# artik530_carrierboard.net
KiCad netlist of a schematic drawn in EAGLE
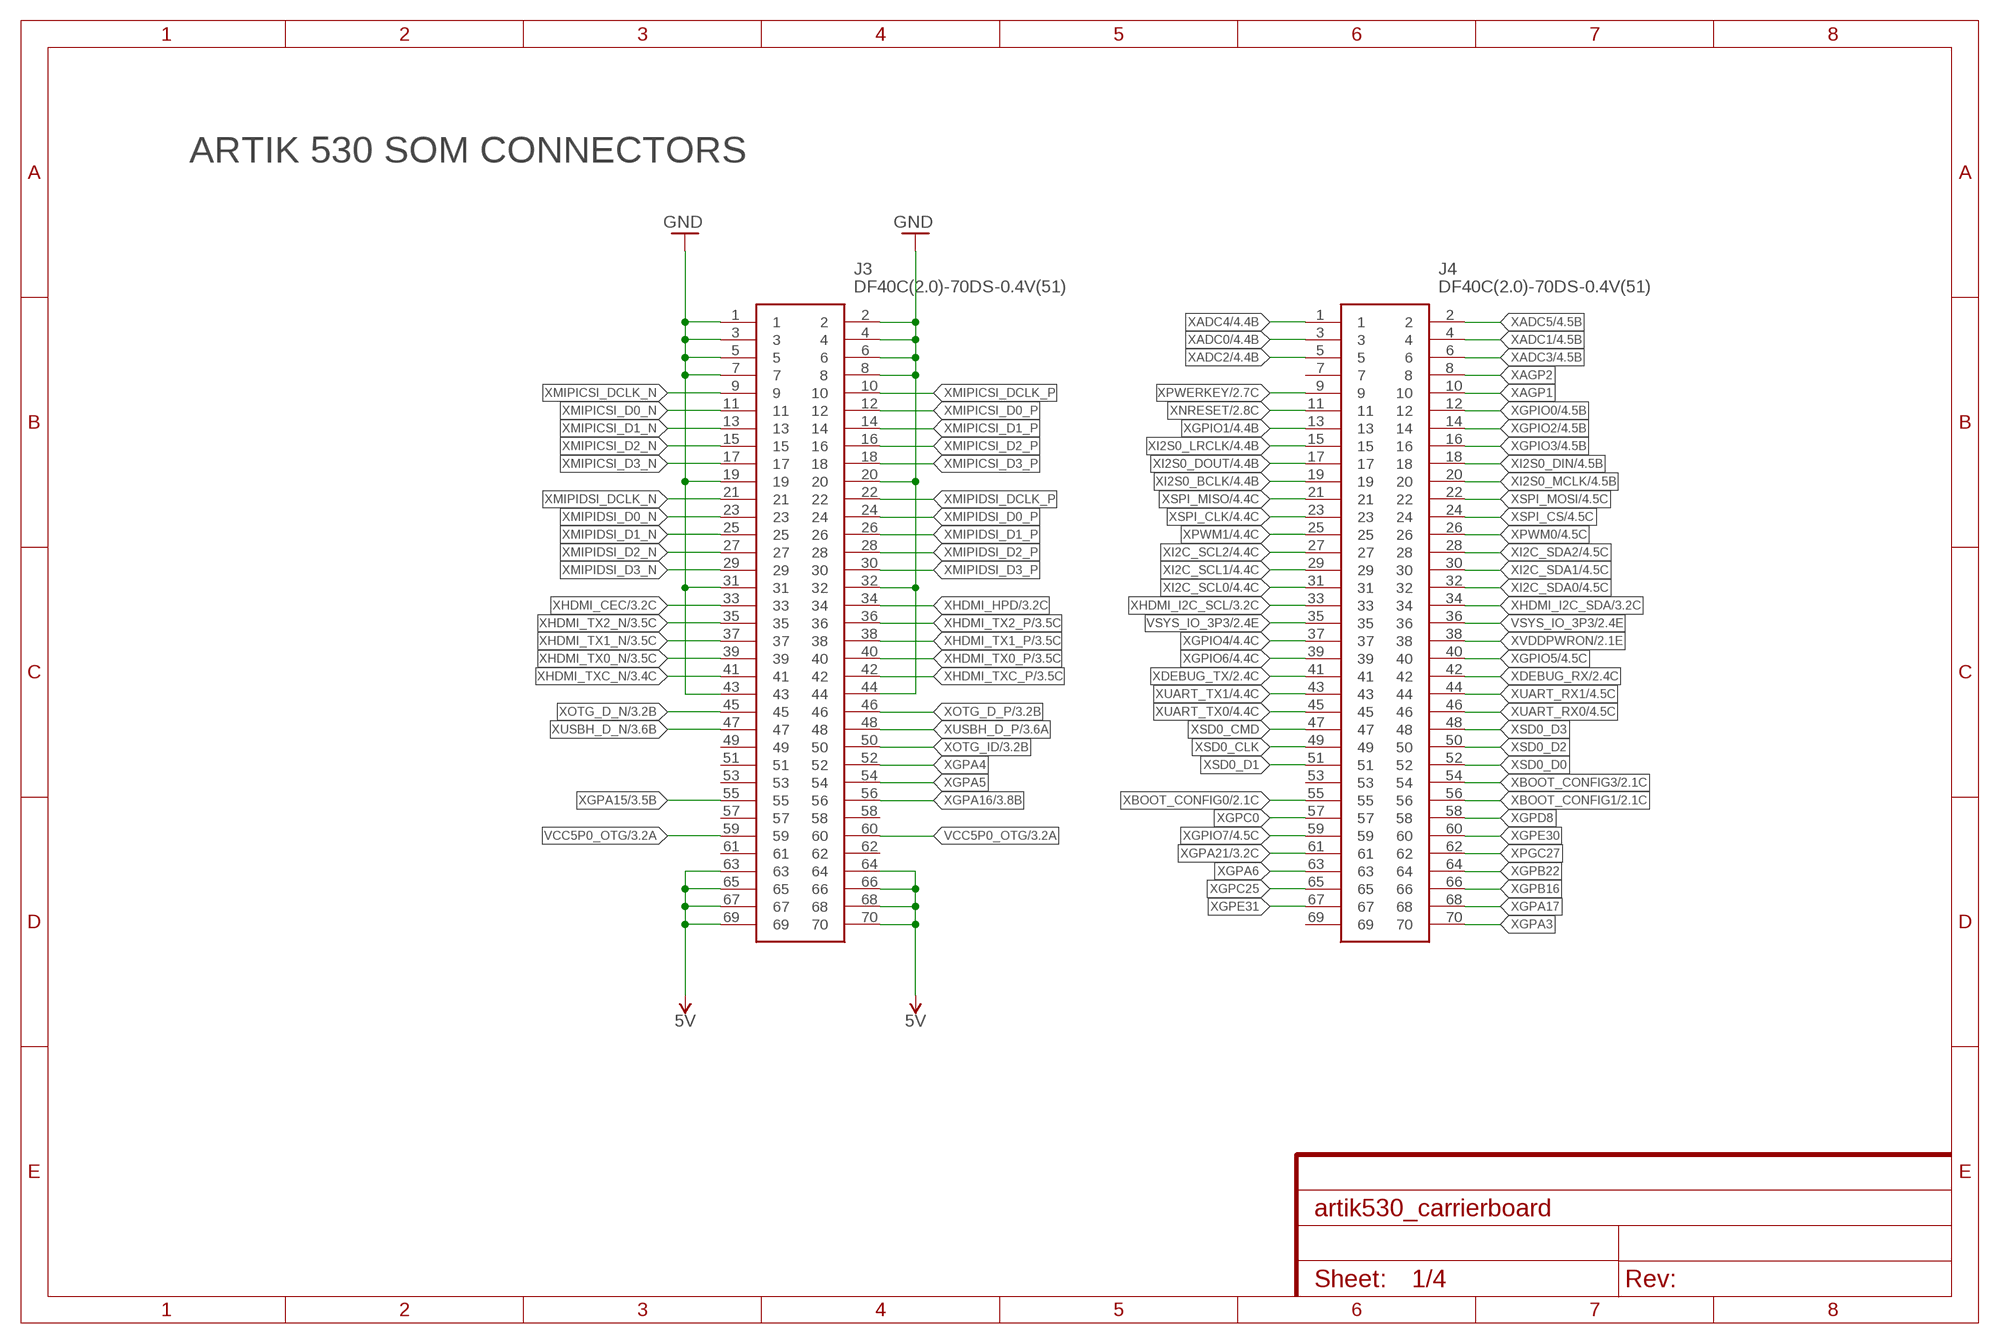
[diagram p0: schematic, sheet 1]
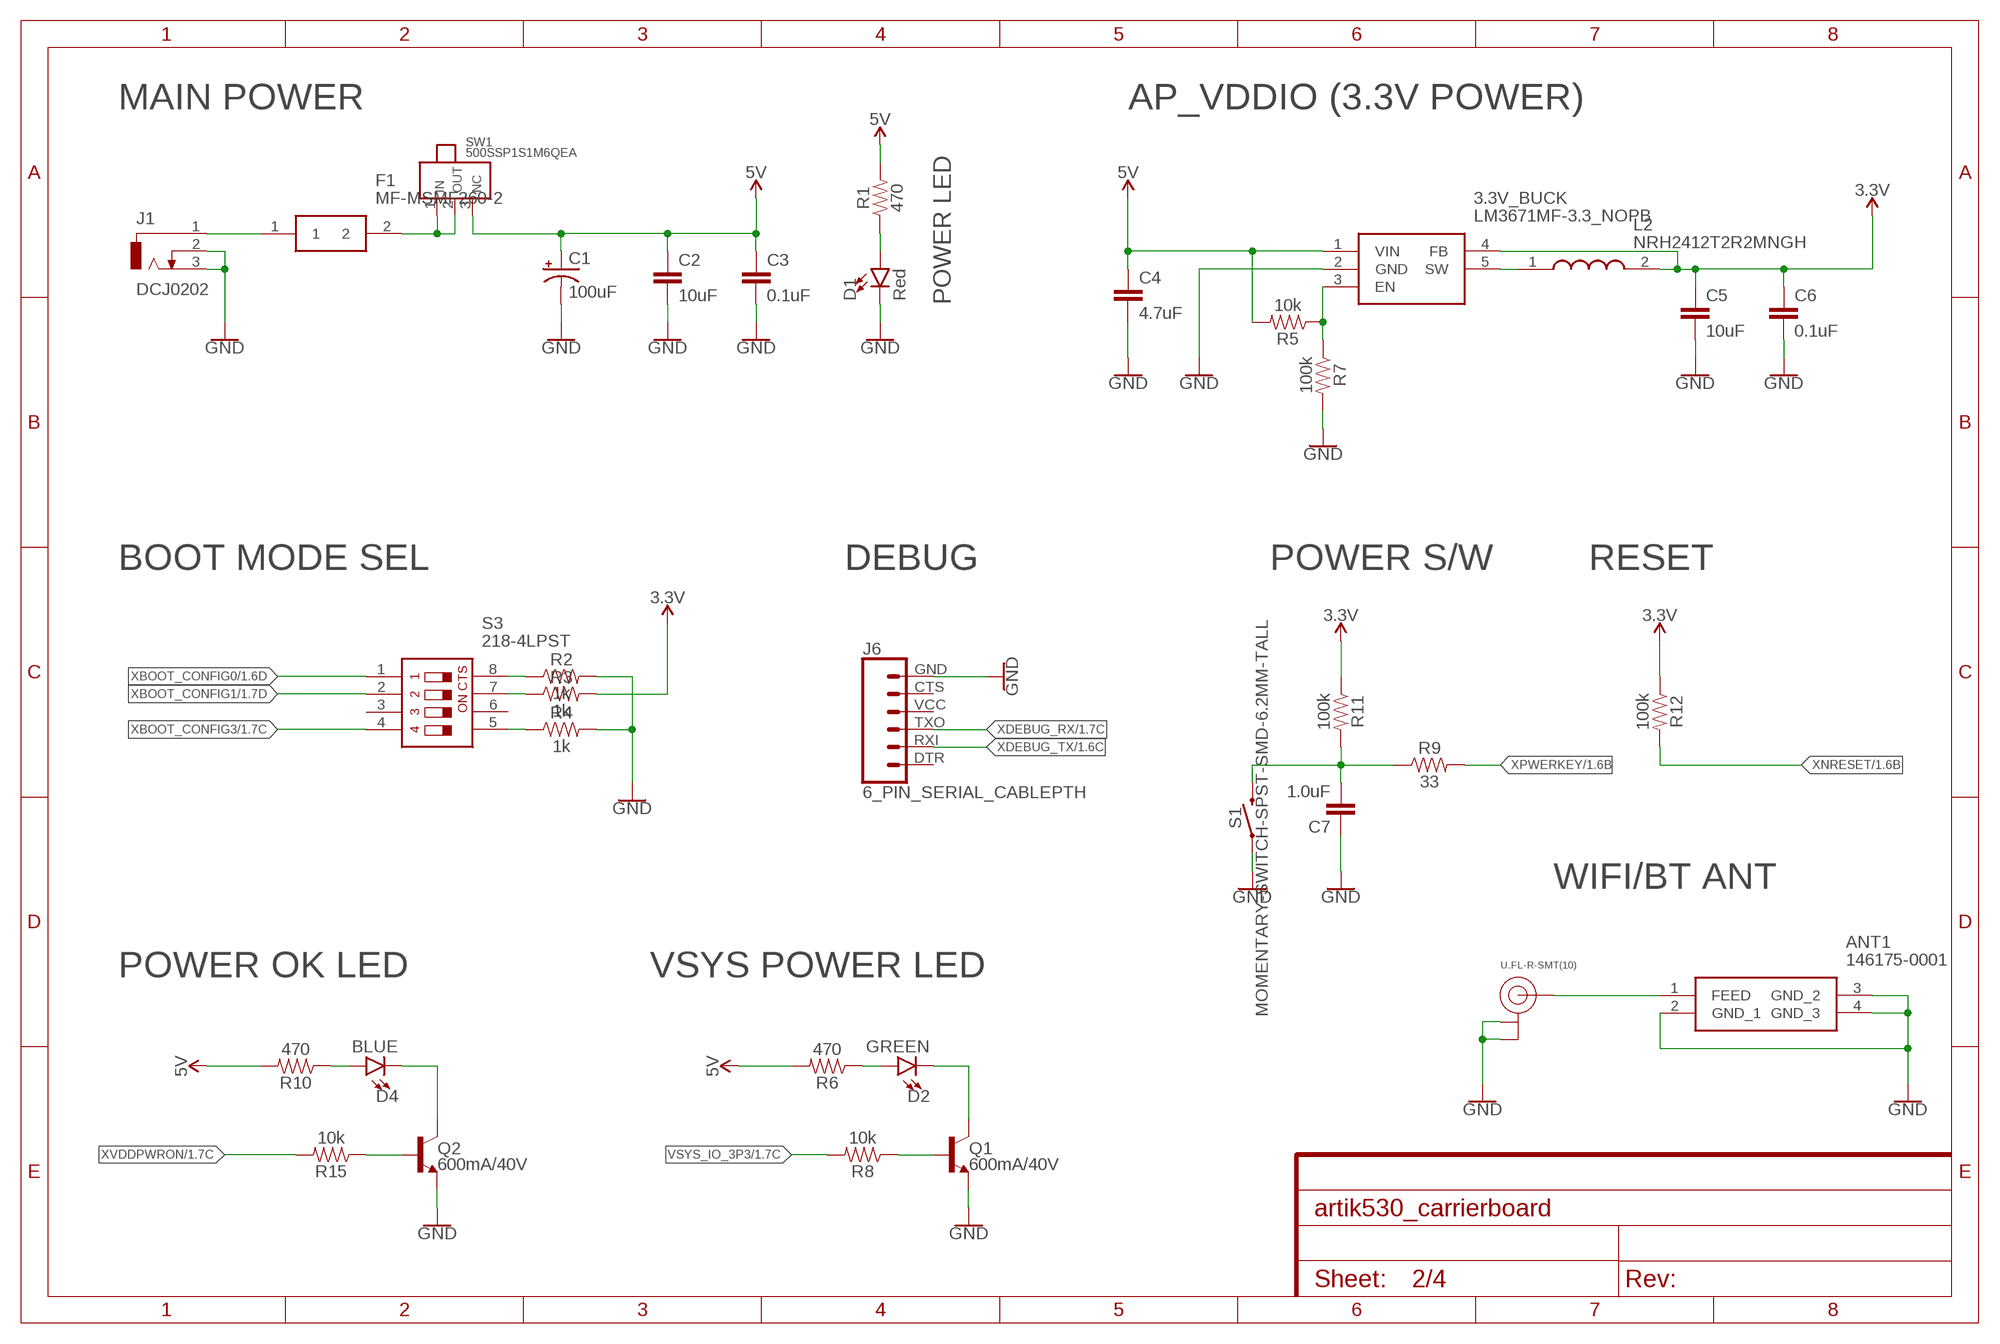
[diagram p1: schematic, sheet 2]
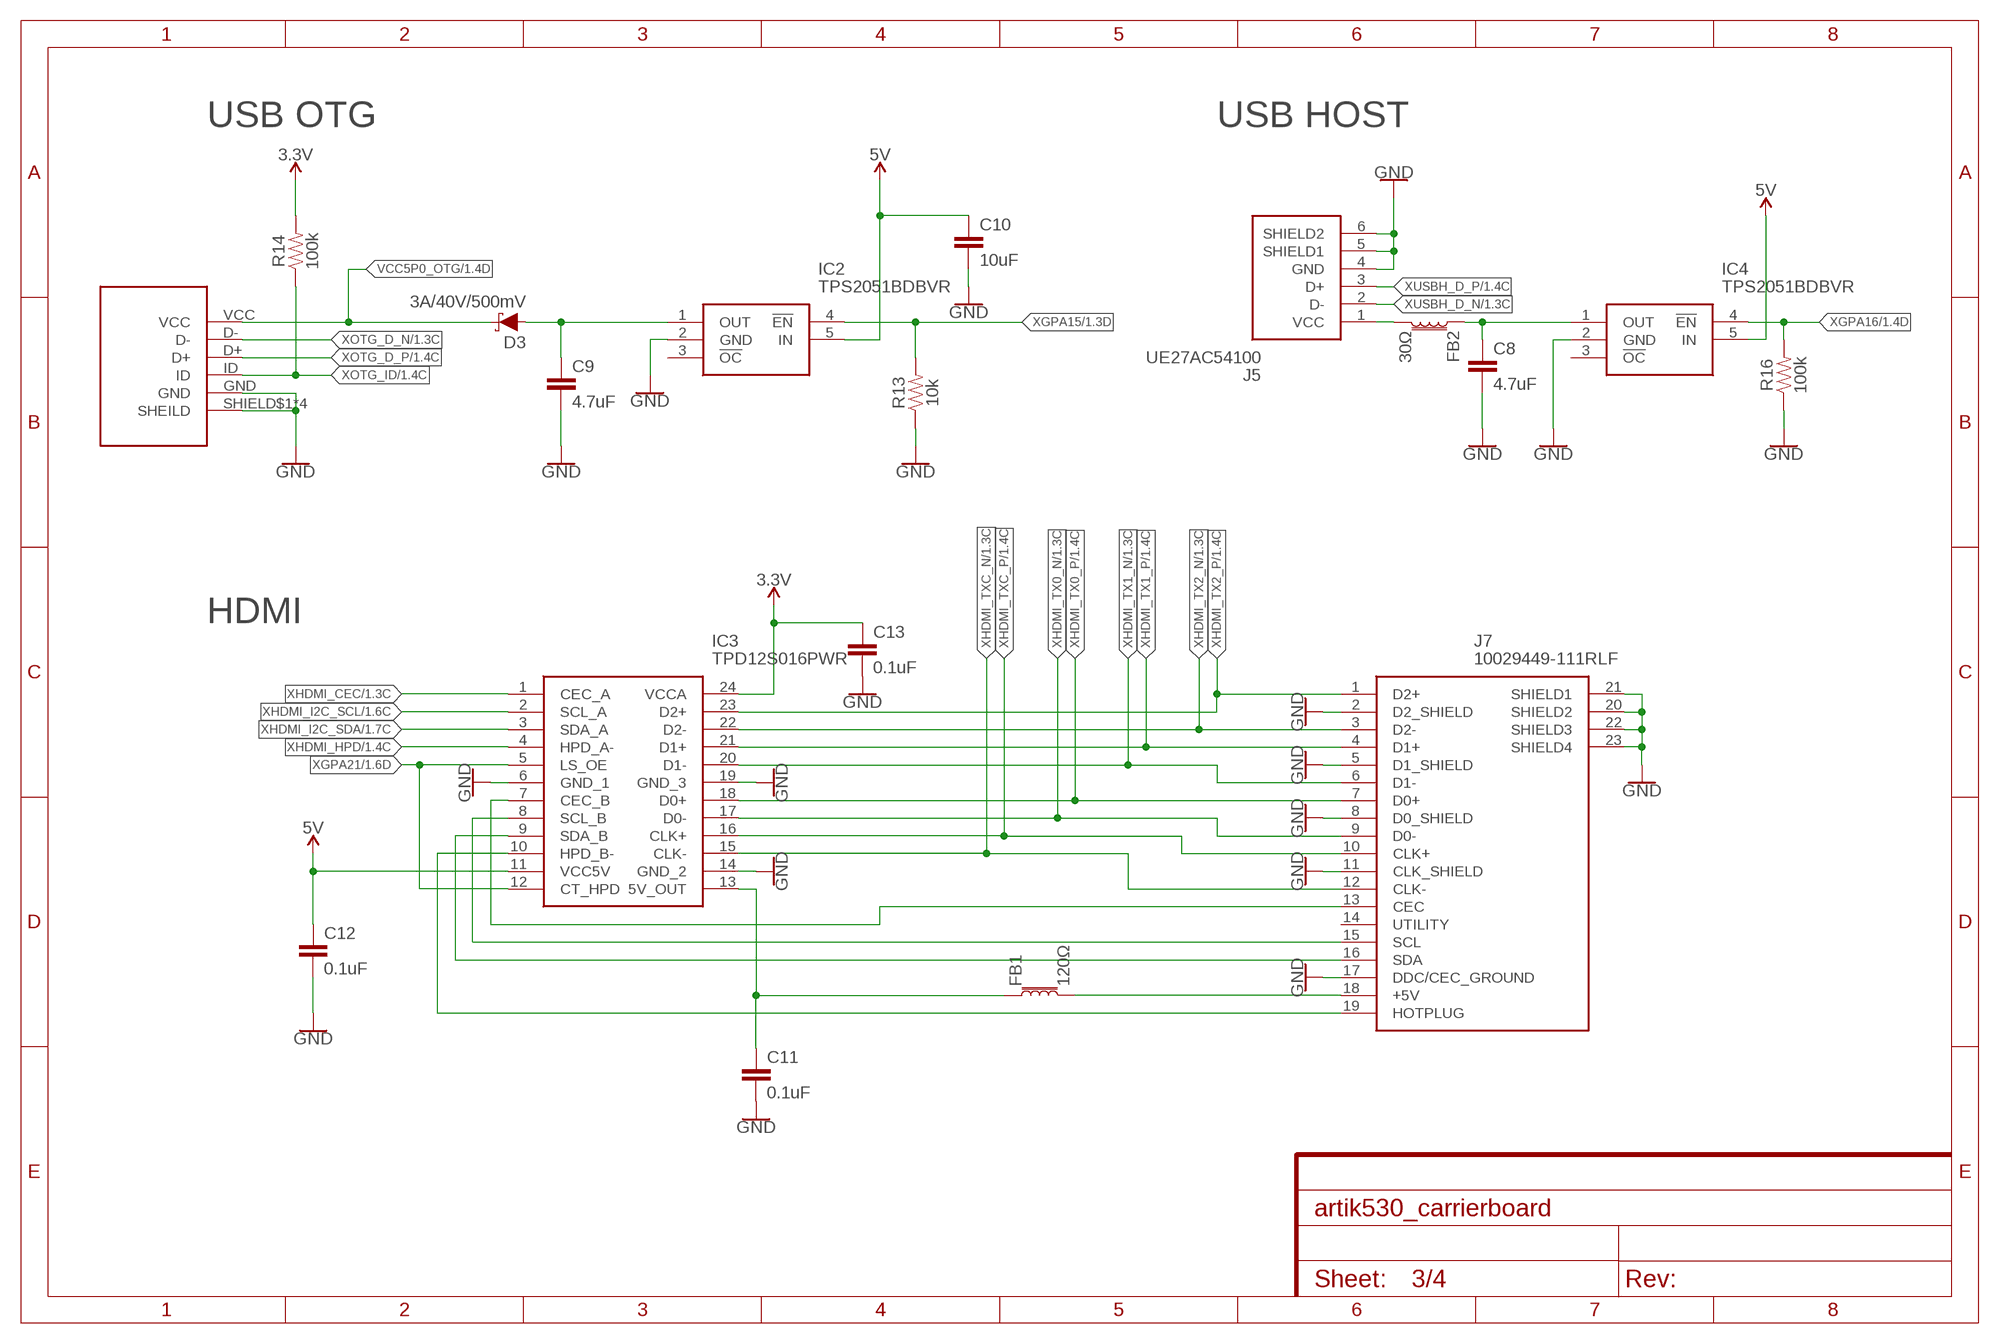
[diagram p2: schematic, sheet 3]
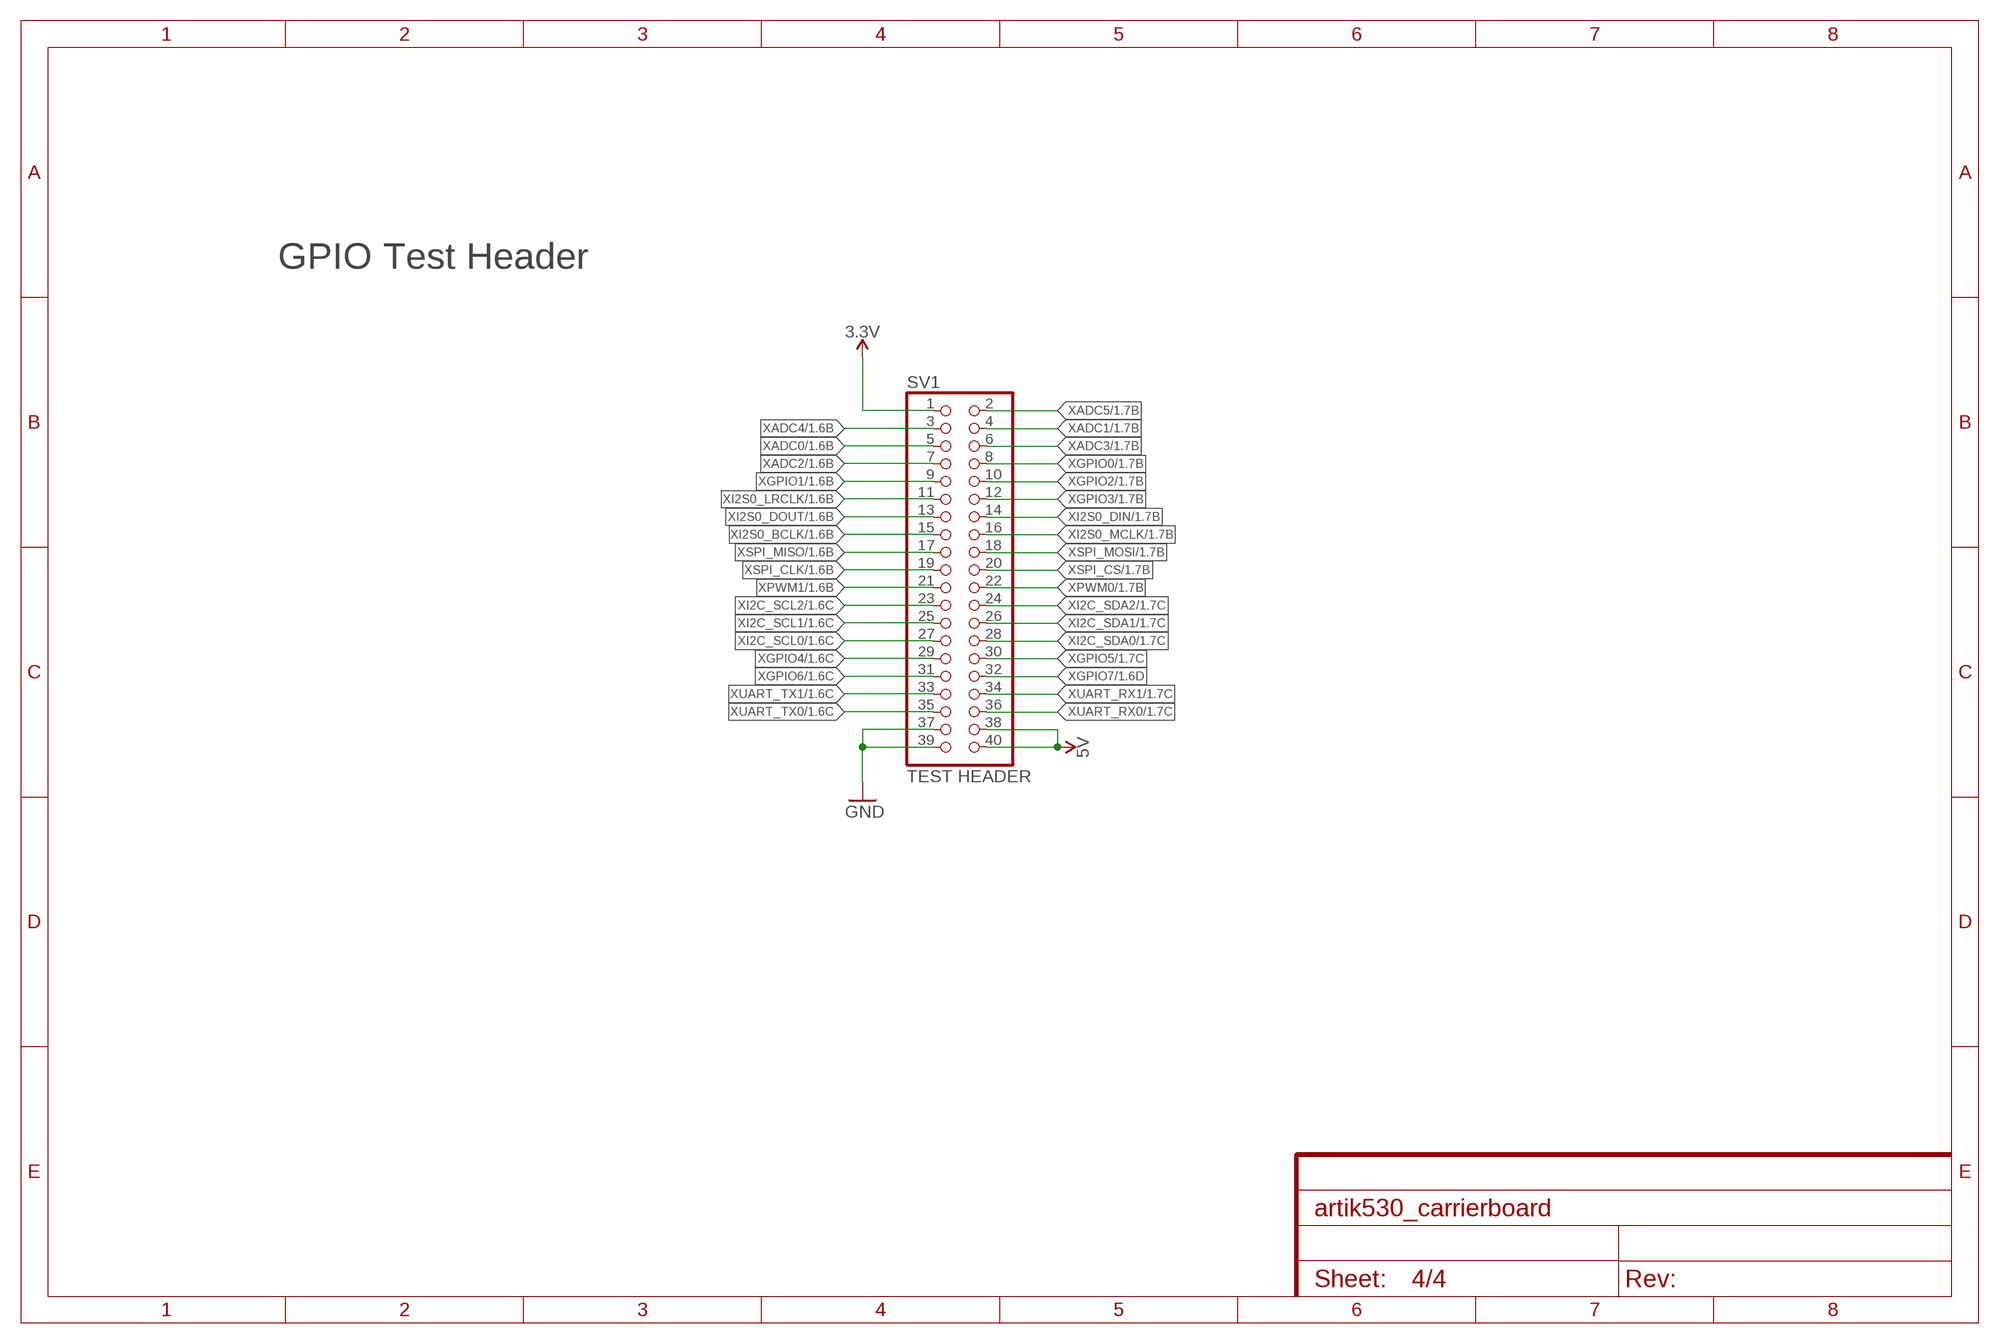
[diagram p3: schematic, sheet 4]

(export (version "E")
  (design (tool "Eeschema 10.0.6"))
  (components
    (comp (ref "C8")
      (value "4.7uF")
      (footprint "eagle-import:0603")
      (libsource (lib "eagle-import") (part "4.7UF-0603-6.3V-(10%)"))
    )
    (comp (ref "C9")
      (value "4.7uF")
      (footprint "eagle-import:0603")
      (libsource (lib "eagle-import") (part "4.7UF-0603-6.3V-(10%)"))
    )
    (comp (ref "C10")
      (value "10uF")
      (footprint "eagle-import:0603")
      (libsource (lib "eagle-import") (part "10UF-0603-6.3V-20%"))
    )
    (comp (ref "C11")
      (value "0.1uF")
      (footprint "eagle-import:0603")
      (libsource (lib "eagle-import") (part "0.1UF-0603-25V-(+80/-20%)"))
    )
    (comp (ref "C12")
      (value "0.1uF")
      (footprint "eagle-import:0603")
      (libsource (lib "eagle-import") (part "0.1UF-0603-25V-(+80/-20%)"))
    )
    (comp (ref "C13")
      (value "0.1uF")
      (footprint "eagle-import:0603")
      (libsource (lib "eagle-import") (part "0.1UF-0603-25V-(+80/-20%)"))
    )
    (comp (ref "D3")
      (value "3A/40V/500mV")
      (footprint "eagle-import:SMA-DIODE")
      (libsource (lib "eagle-import") (part "DIODE-SCHOTTKY-B340A"))
    )
    (comp (ref "FB1")
      (value "120Ω")
      (footprint "eagle-import:0603")
      (libsource (lib "eagle-import") (part "FERRITE_BEAD-0603"))
    )
    (comp (ref "FB2")
      (value "30Ω")
      (footprint "eagle-import:0603")
      (libsource (lib "eagle-import") (part "FERRITE_BEAD-0603"))
    )
    (comp (ref "IC2")
      (value "TPS2051BDBVR")
      (footprint "eagle-import:SOT95P280X145-5N")
      (libsource (lib "eagle-import") (part "TPS2051BDBVR"))
    )
    (comp (ref "IC3")
      (value "TPD12S016PWR")
      (footprint "eagle-import:SOP65P640X120-24N")
      (fields (field (name "RS_PART_NUMBER") "1627865"))
      (libsource (lib "eagle-import") (part "TPD12S016PWR"))
    )
    (comp (ref "IC4")
      (value "TPS2051BDBVR")
      (footprint "eagle-import:SOT95P280X145-5N")
      (libsource (lib "eagle-import") (part "TPS2051BDBVR"))
    )
    (comp (ref "J2")
      (value "10118193-0001LF")
      (footprint "eagle-import:10118193-0001LF")
      (libsource (lib "eagle-import") (part "10118193-0001LF"))
    )
    (comp (ref "J5")
      (value "UE27AC54100")
      (footprint "eagle-import:UE27AC54100")
      (libsource (lib "eagle-import") (part "UE27AC54100"))
    )
    (comp (ref "J7")
      (value "10029449-111RLF")
      (footprint "eagle-import:10029449-111RLF_1")
      (libsource (lib "eagle-import") (part "10029449-111RLF"))
    )
    (comp (ref "R13")
      (value "10k")
      (footprint "eagle-import:0603")
      (libsource (lib "eagle-import") (part "10KOHM-0603-1/10W-1%"))
    )
    (comp (ref "R14")
      (value "100k")
      (footprint "eagle-import:0603")
      (libsource (lib "eagle-import") (part "100KOHM-0603-1/10W-1%"))
    )
    (comp (ref "R16")
      (value "100k")
      (footprint "eagle-import:0603")
      (libsource (lib "eagle-import") (part "100KOHM-0603-1/10W-1%"))
    )
    (comp (ref "3.3V_BUCK")
      (value "LM3671MF-3.3_NOPB")
      (footprint "eagle-import:SOT95P284X122-5N")
      (fields
        (field (name "DIGIKEY_PART_NUMBER") "LM3671MF-3.3/NOPBTR-ND")
        (field (name "MANUFACTURER_PART_NUMBER") "LM3671MF-3.3/NOPB")
      )
      (libsource (lib "eagle-import") (part "LM3671MF-3.3_NOPB"))
    )
    (comp (ref "ANT1")
      (value "146175-0001")
      (footprint "eagle-import:146175-0001")
      (libsource (lib "eagle-import") (part "146175-0001"))
    )
    (comp (ref "C1")
      (value "100uF")
      (footprint "eagle-import:EIA7343")
      (libsource (lib "eagle-import") (part "100UF-POLAR-EIA7343-10V-10%(TANT)"))
    )
    (comp (ref "C2")
      (value "10uF")
      (footprint "eagle-import:0603")
      (libsource (lib "eagle-import") (part "10UF-0603-6.3V-20%"))
    )
    (comp (ref "C3")
      (value "0.1uF")
      (footprint "eagle-import:0603")
      (libsource (lib "eagle-import") (part "0.1UF-0603-25V-(+80/-20%)"))
    )
    (comp (ref "C4")
      (value "4.7uF")
      (footprint "eagle-import:0603")
      (libsource (lib "eagle-import") (part "4.7UF-0603-6.3V-(10%)"))
    )
    (comp (ref "C5")
      (value "10uF")
      (footprint "eagle-import:0603")
      (libsource (lib "eagle-import") (part "10UF-0603-6.3V-20%"))
    )
    (comp (ref "C6")
      (value "0.1uF")
      (footprint "eagle-import:0603")
      (libsource (lib "eagle-import") (part "0.1UF-0603-25V-(+80/-20%)"))
    )
    (comp (ref "C7")
      (value "1.0uF")
      (footprint "eagle-import:0603")
      (libsource (lib "eagle-import") (part "1.0UF-0603-16V-10%"))
    )
    (comp (ref "D1")
      (value "Red")
      (footprint "eagle-import:LED-0603")
      (libsource (lib "eagle-import") (part "LED-RED0603-SMART"))
    )
    (comp (ref "D2")
      (value "GREEN")
      (footprint "eagle-import:LED-0603")
      (libsource (lib "eagle-import") (part "LED-GREEN0603"))
    )
    (comp (ref "D4")
      (value "BLUE")
      (footprint "eagle-import:LED-0603")
      (libsource (lib "eagle-import") (part "LED-GREEN0603"))
    )
    (comp (ref "F1")
      (value "MF-MSMF260-2")
      (footprint "eagle-import:MF-MSMF260-2")
      (fields (field (name "RS_PART_NUMBER") "6478257P"))
      (libsource (lib "eagle-import") (part "MF-MSMF260-2"))
    )
    (comp (ref "J1")
      (value "DCJ0202")
      (footprint "eagle-import:DCJ0202")
      (libsource (lib "eagle-import") (part "DCJ0202"))
    )
    (comp (ref "J6")
      (value "6_PIN_SERIAL_CABLEPTH")
      (footprint "eagle-import:FTDI_BASIC")
      (libsource (lib "eagle-import") (part "6_PIN_SERIAL_CABLEPTH"))
    )
    (comp (ref "L2")
      (value "NRH2412T2R2MNGH")
      (footprint "eagle-import:NRH2412T2R2MNGH")
      (libsource (lib "eagle-import") (part "NRH2412T2R2MNGH"))
    )
    (comp (ref "Q1")
      (value "600mA/40V")
      (footprint "eagle-import:SOT23-3")
      (libsource (lib "eagle-import") (part "TRANS_NPN-MMBT2222AL"))
    )
    (comp (ref "Q2")
      (value "600mA/40V")
      (footprint "eagle-import:SOT23-3")
      (libsource (lib "eagle-import") (part "TRANS_NPN-MMBT2222AL"))
    )
    (comp (ref "R1")
      (value "470")
      (footprint "eagle-import:0603")
      (libsource (lib "eagle-import") (part "470OHM-0603-1/10W-1%"))
    )
    (comp (ref "R2")
      (value "1k")
      (footprint "eagle-import:0603")
      (libsource (lib "eagle-import") (part "1KOHM-0603-1/10W-1%"))
    )
    (comp (ref "R3")
      (value "1k")
      (footprint "eagle-import:0603")
      (libsource (lib "eagle-import") (part "1KOHM-0603-1/10W-1%"))
    )
    (comp (ref "R4")
      (value "1k")
      (footprint "eagle-import:0603")
      (libsource (lib "eagle-import") (part "1KOHM-0603-1/10W-1%"))
    )
    (comp (ref "R5")
      (value "10k")
      (footprint "eagle-import:0603")
      (libsource (lib "eagle-import") (part "10KOHM-0603-1/10W-1%"))
    )
    (comp (ref "R6")
      (value "470")
      (footprint "eagle-import:0603")
      (libsource (lib "eagle-import") (part "470OHM-0603-1/10W-1%"))
    )
    (comp (ref "R7")
      (value "100k")
      (footprint "eagle-import:0603")
      (libsource (lib "eagle-import") (part "100KOHM-0603-1/10W-1%"))
    )
    (comp (ref "R8")
      (value "10k")
      (footprint "eagle-import:0603")
      (libsource (lib "eagle-import") (part "10KOHM-0603-1/10W-1%"))
    )
    (comp (ref "R9")
      (value "33")
      (footprint "eagle-import:0603")
      (libsource (lib "eagle-import") (part "33OHM-0603-1/10W-1%"))
    )
    (comp (ref "R10")
      (value "470")
      (footprint "eagle-import:0603")
      (libsource (lib "eagle-import") (part "470OHM-0603-1/10W-1%"))
    )
    (comp (ref "R11")
      (value "100k")
      (footprint "eagle-import:0603")
      (libsource (lib "eagle-import") (part "100KOHM-0603-1/10W-1%"))
    )
    (comp (ref "R12")
      (value "100k")
      (footprint "eagle-import:0603")
      (libsource (lib "eagle-import") (part "100KOHM-0603-1/10W-1%"))
    )
    (comp (ref "R15")
      (value "10k")
      (footprint "eagle-import:0603")
      (libsource (lib "eagle-import") (part "10KOHM-0603-1/10W-1%"))
    )
    (comp (ref "S1")
      (value "MOMENTARY-SWITCH-SPST-SMD-6.2MM-TALL")
      (footprint "eagle-import:TACTILE_SWITCH_SMD_6.2MM_TALL")
      (libsource (lib "eagle-import") (part "MOMENTARY-SWITCH-SPST-SMD-6.2MM-TALL"))
    )
    (comp (ref "S3")
      (value "218-4LPST")
      (footprint "eagle-import:SOIC127P844X265-8N")
      (libsource (lib "eagle-import") (part "218-4LPST"))
    )
    (comp (ref "SW1")
      (value "500SSP1S1M6QEA")
      (footprint "eagle-import:500SSP1S1M6QEA")
      (libsource (lib "eagle-import") (part "500SSP1S1M6QEA"))
    )
    (comp (ref "U$3")
      (value "U.FL-R-SMT(10)")
      (footprint "eagle-import:U.FL-R-SMT(10)")
      (libsource (lib "eagle-import") (part "U.FL-R-SMT(10)"))
    )
    (comp (ref "J3")
      (value "DF40C(2.0)-70DS-0.4V(51)")
      (footprint "eagle-import:DF40C(2.0)-70DS-0.4V(51)")
      (libsource (lib "eagle-import") (part "DF40C(2.0)-70DS-0.4V(51)"))
    )
    (comp (ref "J4")
      (value "DF40C(2.0)-70DS-0.4V(51)")
      (footprint "eagle-import:DF40C(2.0)-70DS-0.4V(51)")
      (libsource (lib "eagle-import") (part "DF40C(2.0)-70DS-0.4V(51)"))
    )
    (comp (ref "SV1")
      (value "TEST HEADER")
      (footprint "eagle-import:2X20")
      (libsource (lib "eagle-import") (part "PINHD-2X20"))
    )
  )
  (nets
    (net (code "1") (name "3.3V") (class "Default")
      (node (ref "3.3V_BUCK") (pin "4") (pinfunction "FB_4") (pintype "bidirectional"))
      (node (ref "C13") (pin "1") (pinfunction "1_1") (pintype "passive"))
      (node (ref "C5") (pin "1") (pinfunction "1_1") (pintype "passive"))
      (node (ref "C6") (pin "1") (pinfunction "1_1") (pintype "passive"))
      (node (ref "IC3") (pin "24") (pinfunction "VCCA_24") (pintype "bidirectional"))
      (node (ref "L2") (pin "2") (pinfunction "2_2") (pintype "bidirectional"))
      (node (ref "R11") (pin "1") (pinfunction "1_1") (pintype "passive"))
      (node (ref "R12") (pin "1") (pinfunction "1_1") (pintype "passive"))
      (node (ref "R14") (pin "2") (pinfunction "2_2") (pintype "passive"))
      (node (ref "R3") (pin "2") (pinfunction "2_2") (pintype "passive"))
      (node (ref "SV1") (pin "1") (pinfunction "1_1") (pintype "passive"))
    )
    (net (code "2") (name "5V") (class "Default")
      (node (ref "3.3V_BUCK") (pin "1") (pinfunction "VIN_1") (pintype "bidirectional"))
      (node (ref "C1") (pin "A") (pinfunction "+_A") (pintype "passive"))
      (node (ref "C10") (pin "1") (pinfunction "1_1") (pintype "passive"))
      (node (ref "C12") (pin "1") (pinfunction "1_1") (pintype "passive"))
      (node (ref "C2") (pin "1") (pinfunction "1_1") (pintype "passive"))
      (node (ref "C3") (pin "1") (pinfunction "1_1") (pintype "passive"))
      (node (ref "C4") (pin "1") (pinfunction "1_1") (pintype "passive"))
      (node (ref "IC2") (pin "5") (pinfunction "IN_5") (pintype "input"))
      (node (ref "IC3") (pin "11") (pinfunction "VCC5V_11") (pintype "bidirectional"))
      (node (ref "IC4") (pin "5") (pinfunction "IN_5") (pintype "input"))
      (node (ref "J3") (pin "63") (pinfunction "63_63") (pintype "bidirectional"))
      (node (ref "J3") (pin "64") (pinfunction "64_64") (pintype "bidirectional"))
      (node (ref "J3") (pin "65") (pinfunction "65_65") (pintype "bidirectional"))
      (node (ref "J3") (pin "66") (pinfunction "66_66") (pintype "bidirectional"))
      (node (ref "J3") (pin "67") (pinfunction "67_67") (pintype "bidirectional"))
      (node (ref "J3") (pin "68") (pinfunction "68_68") (pintype "bidirectional"))
      (node (ref "J3") (pin "69") (pinfunction "69_69") (pintype "bidirectional"))
      (node (ref "J3") (pin "70") (pinfunction "70_70") (pintype "bidirectional"))
      (node (ref "R1") (pin "2") (pinfunction "2_2") (pintype "passive"))
      (node (ref "R10") (pin "2") (pinfunction "2_2") (pintype "passive"))
      (node (ref "R5") (pin "2") (pinfunction "2_2") (pintype "passive"))
      (node (ref "R6") (pin "2") (pinfunction "2_2") (pintype "passive"))
      (node (ref "SV1") (pin "38") (pinfunction "38_38") (pintype "passive"))
      (node (ref "SV1") (pin "40") (pinfunction "40_40") (pintype "passive"))
      (node (ref "SW1") (pin "3") (pinfunction "NC_3") (pintype "bidirectional"))
    )
    (net (code "3") (name "GND") (class "Default")
      (node (ref "3.3V_BUCK") (pin "2") (pinfunction "GND_2") (pintype "bidirectional"))
      (node (ref "ANT1") (pin "2") (pinfunction "GND_1_2") (pintype "bidirectional"))
      (node (ref "ANT1") (pin "3") (pinfunction "GND_2_3") (pintype "bidirectional"))
      (node (ref "ANT1") (pin "4") (pinfunction "GND_3_4") (pintype "bidirectional"))
      (node (ref "C1") (pin "C") (pinfunction "-_C") (pintype "passive"))
      (node (ref "C10") (pin "2") (pinfunction "2_2") (pintype "passive"))
      (node (ref "C11") (pin "2") (pinfunction "2_2") (pintype "passive"))
      (node (ref "C12") (pin "2") (pinfunction "2_2") (pintype "passive"))
      (node (ref "C13") (pin "2") (pinfunction "2_2") (pintype "passive"))
      (node (ref "C2") (pin "2") (pinfunction "2_2") (pintype "passive"))
      (node (ref "C3") (pin "2") (pinfunction "2_2") (pintype "passive"))
      (node (ref "C4") (pin "2") (pinfunction "2_2") (pintype "passive"))
      (node (ref "C5") (pin "2") (pinfunction "2_2") (pintype "passive"))
      (node (ref "C6") (pin "2") (pinfunction "2_2") (pintype "passive"))
      (node (ref "C7") (pin "1") (pinfunction "1_1") (pintype "passive"))
      (node (ref "C8") (pin "2") (pinfunction "2_2") (pintype "passive"))
      (node (ref "C9") (pin "2") (pinfunction "2_2") (pintype "passive"))
      (node (ref "D1") (pin "C") (pinfunction "C_C") (pintype "passive"))
      (node (ref "IC2") (pin "2") (pinfunction "GND_2") (pintype "power_in"))
      (node (ref "IC3") (pin "14") (pinfunction "GND_2_14") (pintype "bidirectional"))
      (node (ref "IC3") (pin "19") (pinfunction "GND_3_19") (pintype "bidirectional"))
      (node (ref "IC3") (pin "6") (pinfunction "GND_1_6") (pintype "bidirectional"))
      (node (ref "IC4") (pin "2") (pinfunction "GND_2") (pintype "power_in"))
      (node (ref "J1") (pin "2") (pinfunction "2_2") (pintype "passive"))
      (node (ref "J1") (pin "3") (pinfunction "3_3") (pintype "passive"))
      (node (ref "J2") (pin "GND") (pinfunction "GND_GND") (pintype "bidirectional"))
      (node (ref "J2") (pin "SHIELD$1") (pinfunction "SHEILD_SHIELD$1") (pintype "bidirectional"))
      (node (ref "J2") (pin "SHIELD$2") (pinfunction "SHEILD_SHIELD$2") (pintype "bidirectional"))
      (node (ref "J2") (pin "SHIELD$3") (pinfunction "SHEILD_SHIELD$3") (pintype "bidirectional"))
      (node (ref "J2") (pin "SHIELD$4") (pinfunction "SHEILD_SHIELD$4") (pintype "bidirectional"))
      (node (ref "J3") (pin "1") (pinfunction "1_1") (pintype "bidirectional"))
      (node (ref "J3") (pin "19") (pinfunction "19_19") (pintype "bidirectional"))
      (node (ref "J3") (pin "2") (pinfunction "2_2") (pintype "bidirectional"))
      (node (ref "J3") (pin "20") (pinfunction "20_20") (pintype "bidirectional"))
      (node (ref "J3") (pin "3") (pinfunction "3_3") (pintype "bidirectional"))
      (node (ref "J3") (pin "31") (pinfunction "31_31") (pintype "bidirectional"))
      (node (ref "J3") (pin "32") (pinfunction "32_32") (pintype "bidirectional"))
      (node (ref "J3") (pin "4") (pinfunction "4_4") (pintype "bidirectional"))
      (node (ref "J3") (pin "43") (pinfunction "43_43") (pintype "bidirectional"))
      (node (ref "J3") (pin "44") (pinfunction "44_44") (pintype "bidirectional"))
      (node (ref "J3") (pin "5") (pinfunction "5_5") (pintype "bidirectional"))
      (node (ref "J3") (pin "6") (pinfunction "6_6") (pintype "bidirectional"))
      (node (ref "J3") (pin "7") (pinfunction "7_7") (pintype "bidirectional"))
      (node (ref "J3") (pin "8") (pinfunction "8_8") (pintype "bidirectional"))
      (node (ref "J5") (pin "4") (pinfunction "GND_4") (pintype "bidirectional"))
      (node (ref "J5") (pin "5") (pinfunction "SHIELD1_5") (pintype "bidirectional"))
      (node (ref "J5") (pin "6") (pinfunction "SHIELD2_6") (pintype "bidirectional"))
      (node (ref "J6") (pin "GND") (pinfunction "6_GND") (pintype "passive"))
      (node (ref "J7") (pin "11") (pinfunction "CLK_SHIELD_11") (pintype "bidirectional"))
      (node (ref "J7") (pin "17") (pinfunction "DDC/CEC_GROUND_17") (pintype "bidirectional"))
      (node (ref "J7") (pin "2") (pinfunction "D2_SHIELD_2") (pintype "bidirectional"))
      (node (ref "J7") (pin "20") (pinfunction "SHIELD2_20") (pintype "bidirectional"))
      (node (ref "J7") (pin "21") (pinfunction "SHIELD1_21") (pintype "bidirectional"))
      (node (ref "J7") (pin "22") (pinfunction "SHIELD3_22") (pintype "bidirectional"))
      (node (ref "J7") (pin "23") (pinfunction "SHIELD4_23") (pintype "bidirectional"))
      (node (ref "J7") (pin "5") (pinfunction "D1_SHIELD_5") (pintype "bidirectional"))
      (node (ref "J7") (pin "8") (pinfunction "D0_SHIELD_8") (pintype "bidirectional"))
      (node (ref "Q1") (pin "2") (pinfunction "E_2") (pintype "passive"))
      (node (ref "Q2") (pin "2") (pinfunction "E_2") (pintype "passive"))
      (node (ref "R13") (pin "1") (pinfunction "1_1") (pintype "passive"))
      (node (ref "R16") (pin "1") (pinfunction "1_1") (pintype "passive"))
      (node (ref "R2") (pin "2") (pinfunction "2_2") (pintype "passive"))
      (node (ref "R4") (pin "2") (pinfunction "2_2") (pintype "passive"))
      (node (ref "R7") (pin "2") (pinfunction "2_2") (pintype "passive"))
      (node (ref "S1") (pin "A2") (pinfunction "1_A2") (pintype "passive"))
      (node (ref "SV1") (pin "37") (pinfunction "37_37") (pintype "passive"))
      (node (ref "SV1") (pin "39") (pinfunction "39_39") (pintype "passive"))
      (node (ref "U$3") (pin "1") (pinfunction "GND1_1") (pintype "bidirectional"))
      (node (ref "U$3") (pin "2") (pinfunction "GND2_2") (pintype "bidirectional"))
    )
    (net (code "4") (name "Net-(3.3V_BUCK-EN)") (class "Default")
      (node (ref "3.3V_BUCK") (pin "3") (pinfunction "EN_3") (pintype "bidirectional"))
      (node (ref "R5") (pin "1") (pinfunction "1_1") (pintype "passive"))
      (node (ref "R7") (pin "1") (pinfunction "1_1") (pintype "passive"))
    )
    (net (code "5") (name "Net-(3.3V_BUCK-SW)") (class "Default")
      (node (ref "3.3V_BUCK") (pin "5") (pinfunction "SW_5") (pintype "bidirectional"))
      (node (ref "L2") (pin "1") (pinfunction "1_1") (pintype "bidirectional"))
    )
    (net (code "6") (name "Net-(ANT1-FEED)") (class "Default")
      (node (ref "ANT1") (pin "1") (pinfunction "FEED_1") (pintype "bidirectional"))
      (node (ref "U$3") (pin "3") (pinfunction "SIG_3") (pintype "bidirectional"))
    )
    (net (code "7") (name "Net-(D1-PadA)") (class "Default")
      (node (ref "D1") (pin "A") (pinfunction "A_A") (pintype "passive"))
      (node (ref "R1") (pin "1") (pinfunction "1_1") (pintype "passive"))
    )
    (net (code "8") (name "Net-(D2-PadA)") (class "Default")
      (node (ref "D2") (pin "A") (pinfunction "A_A") (pintype "passive"))
      (node (ref "R6") (pin "1") (pinfunction "1_1") (pintype "passive"))
    )
    (net (code "9") (name "Net-(D4-PadA)") (class "Default")
      (node (ref "D4") (pin "A") (pinfunction "A_A") (pintype "passive"))
      (node (ref "R10") (pin "1") (pinfunction "1_1") (pintype "passive"))
    )
    (net (code "10") (name "Net-(F1-Pad1)") (class "Default")
      (node (ref "F1") (pin "1") (pinfunction "1_1") (pintype "bidirectional"))
      (node (ref "J1") (pin "1") (pinfunction "1_1") (pintype "passive"))
    )
    (net (code "11") (name "Net-(IC2-OUT)") (class "Default")
      (node (ref "C9") (pin "1") (pinfunction "1_1") (pintype "passive"))
      (node (ref "D3") (pin "A") (pinfunction "A_A") (pintype "passive"))
      (node (ref "IC2") (pin "1") (pinfunction "OUT_1") (pintype "output"))
    )
    (net (code "12") (name "Net-(IC3-5V_OUT)") (class "Default")
      (node (ref "C11") (pin "1") (pinfunction "1_1") (pintype "passive"))
      (node (ref "FB1") (pin "1") (pinfunction "1_1") (pintype "passive"))
      (node (ref "IC3") (pin "13") (pinfunction "5V_OUT_13") (pintype "output"))
    )
    (net (code "13") (name "Net-(IC3-CEC_B)") (class "Default")
      (node (ref "IC3") (pin "7") (pinfunction "CEC_B_7") (pintype "bidirectional"))
      (node (ref "J7") (pin "13") (pinfunction "CEC_13") (pintype "bidirectional"))
    )
    (net (code "14") (name "Net-(IC3-HPD_B-)") (class "Default")
      (node (ref "IC3") (pin "10") (pinfunction "HPD_B-_10") (pintype "bidirectional"))
      (node (ref "J7") (pin "19") (pinfunction "HOTPLUG_19") (pintype "bidirectional"))
    )
    (net (code "15") (name "Net-(IC3-SCL_B)") (class "Default")
      (node (ref "IC3") (pin "8") (pinfunction "SCL_B_8") (pintype "bidirectional"))
      (node (ref "J7") (pin "15") (pinfunction "SCL_15") (pintype "bidirectional"))
    )
    (net (code "16") (name "Net-(IC3-SDA_B)") (class "Default")
      (node (ref "IC3") (pin "9") (pinfunction "SDA_B_9") (pintype "bidirectional"))
      (node (ref "J7") (pin "16") (pinfunction "SDA_16") (pintype "bidirectional"))
    )
    (net (code "17") (name "Net-(IC4-OUT)") (class "Default")
      (node (ref "C8") (pin "1") (pinfunction "1_1") (pintype "passive"))
      (node (ref "FB2") (pin "1") (pinfunction "1_1") (pintype "passive"))
      (node (ref "IC4") (pin "1") (pinfunction "OUT_1") (pintype "output"))
    )
    (net (code "18") (name "Net-(J5-VCC)") (class "Default")
      (node (ref "FB2") (pin "2") (pinfunction "2_2") (pintype "passive"))
      (node (ref "J5") (pin "1") (pinfunction "VCC_1") (pintype "bidirectional"))
    )
    (net (code "19") (name "Net-(J7-+5V)") (class "Default")
      (node (ref "FB1") (pin "2") (pinfunction "2_2") (pintype "passive"))
      (node (ref "J7") (pin "18") (pinfunction "+5V_18") (pintype "bidirectional"))
    )
    (net (code "20") (name "Net-(Q1-B)") (class "Default")
      (node (ref "Q1") (pin "1") (pinfunction "B_1") (pintype "passive"))
      (node (ref "R8") (pin "1") (pinfunction "1_1") (pintype "passive"))
    )
    (net (code "21") (name "Net-(Q1-C)") (class "Default")
      (node (ref "D2") (pin "C") (pinfunction "C_C") (pintype "passive"))
      (node (ref "Q1") (pin "3") (pinfunction "C_3") (pintype "passive"))
    )
    (net (code "22") (name "Net-(Q2-B)") (class "Default")
      (node (ref "Q2") (pin "1") (pinfunction "B_1") (pintype "passive"))
      (node (ref "R15") (pin "1") (pinfunction "1_1") (pintype "passive"))
    )
    (net (code "23") (name "Net-(Q2-C)") (class "Default")
      (node (ref "D4") (pin "C") (pinfunction "C_C") (pintype "passive"))
      (node (ref "Q2") (pin "3") (pinfunction "C_3") (pintype "passive"))
    )
    (net (code "24") (name "Net-(R2-Pad1)") (class "Default")
      (node (ref "R2") (pin "1") (pinfunction "1_1") (pintype "passive"))
      (node (ref "S3") (pin "8") (pinfunction "8_8") (pintype "bidirectional"))
    )
    (net (code "25") (name "Net-(R3-Pad1)") (class "Default")
      (node (ref "R3") (pin "1") (pinfunction "1_1") (pintype "passive"))
      (node (ref "S3") (pin "7") (pinfunction "7_7") (pintype "bidirectional"))
    )
    (net (code "26") (name "Net-(R4-Pad1)") (class "Default")
      (node (ref "R4") (pin "1") (pinfunction "1_1") (pintype "passive"))
      (node (ref "S3") (pin "5") (pinfunction "5_5") (pintype "bidirectional"))
    )
    (net (code "27") (name "Net-(S1-2)") (class "Default")
      (node (ref "C7") (pin "2") (pinfunction "2_2") (pintype "passive"))
      (node (ref "R11") (pin "2") (pinfunction "2_2") (pintype "passive"))
      (node (ref "R9") (pin "1") (pinfunction "1_1") (pintype "passive"))
      (node (ref "S1") (pin "B2") (pinfunction "2_B2") (pintype "passive"))
    )
    (net (code "28") (name "Net-(SW1-IN)") (class "Default")
      (node (ref "F1") (pin "2") (pinfunction "2_2") (pintype "bidirectional"))
      (node (ref "SW1") (pin "1") (pinfunction "IN_1") (pintype "bidirectional"))
      (node (ref "SW1") (pin "2") (pinfunction "OUT_2") (pintype "bidirectional"))
    )
    (net (code "29") (name "VCC5P0_OTG") (class "Default")
      (node (ref "D3") (pin "C") (pinfunction "C_C") (pintype "passive"))
      (node (ref "J2") (pin "VCC") (pinfunction "VCC_VCC") (pintype "bidirectional"))
      (node (ref "J3") (pin "59") (pinfunction "59_59") (pintype "bidirectional"))
      (node (ref "J3") (pin "60") (pinfunction "60_60") (pintype "bidirectional"))
    )
    (net (code "30") (name "VSYS_IO_3P3") (class "Default")
      (node (ref "J4") (pin "35") (pinfunction "35_35") (pintype "bidirectional"))
      (node (ref "J4") (pin "36") (pinfunction "36_36") (pintype "bidirectional"))
      (node (ref "R8") (pin "2") (pinfunction "2_2") (pintype "passive"))
    )
    (net (code "31") (name "XADC0") (class "Default")
      (node (ref "J4") (pin "3") (pinfunction "3_3") (pintype "bidirectional"))
      (node (ref "SV1") (pin "5") (pinfunction "5_5") (pintype "passive"))
    )
    (net (code "32") (name "XADC1") (class "Default")
      (node (ref "J4") (pin "4") (pinfunction "4_4") (pintype "bidirectional"))
      (node (ref "SV1") (pin "4") (pinfunction "4_4") (pintype "passive"))
    )
    (net (code "33") (name "XADC2") (class "Default")
      (node (ref "J4") (pin "5") (pinfunction "5_5") (pintype "bidirectional"))
      (node (ref "SV1") (pin "7") (pinfunction "7_7") (pintype "passive"))
    )
    (net (code "34") (name "XADC3") (class "Default")
      (node (ref "J4") (pin "6") (pinfunction "6_6") (pintype "bidirectional"))
      (node (ref "SV1") (pin "6") (pinfunction "6_6") (pintype "passive"))
    )
    (net (code "35") (name "XADC4") (class "Default")
      (node (ref "J4") (pin "1") (pinfunction "1_1") (pintype "bidirectional"))
      (node (ref "SV1") (pin "3") (pinfunction "3_3") (pintype "passive"))
    )
    (net (code "36") (name "XADC5") (class "Default")
      (node (ref "J4") (pin "2") (pinfunction "2_2") (pintype "bidirectional"))
      (node (ref "SV1") (pin "2") (pinfunction "2_2") (pintype "passive"))
    )
    (net (code "37") (name "XAGP1") (class "Default")
      (node (ref "J4") (pin "10") (pinfunction "10_10") (pintype "bidirectional"))
    )
    (net (code "38") (name "XAGP2") (class "Default")
      (node (ref "J4") (pin "8") (pinfunction "8_8") (pintype "bidirectional"))
    )
    (net (code "39") (name "XBOOT_CONFIG0") (class "Default")
      (node (ref "J4") (pin "55") (pinfunction "55_55") (pintype "bidirectional"))
      (node (ref "S3") (pin "1") (pinfunction "1_1") (pintype "bidirectional"))
    )
    (net (code "40") (name "XBOOT_CONFIG1") (class "Default")
      (node (ref "J4") (pin "56") (pinfunction "56_56") (pintype "bidirectional"))
      (node (ref "S3") (pin "2") (pinfunction "2_2") (pintype "bidirectional"))
    )
    (net (code "41") (name "XBOOT_CONFIG3") (class "Default")
      (node (ref "J4") (pin "54") (pinfunction "54_54") (pintype "bidirectional"))
      (node (ref "S3") (pin "4") (pinfunction "4_4") (pintype "bidirectional"))
    )
    (net (code "42") (name "XDEBUG_RX") (class "Default")
      (node (ref "J4") (pin "42") (pinfunction "42_42") (pintype "bidirectional"))
      (node (ref "J6") (pin "TXO") (pinfunction "3_TXO") (pintype "passive"))
    )
    (net (code "43") (name "XDEBUG_TX") (class "Default")
      (node (ref "J4") (pin "41") (pinfunction "41_41") (pintype "bidirectional"))
      (node (ref "J6") (pin "RXI") (pinfunction "2_RXI") (pintype "passive"))
    )
    (net (code "44") (name "XGPA3") (class "Default")
      (node (ref "J4") (pin "70") (pinfunction "70_70") (pintype "bidirectional"))
    )
    (net (code "45") (name "XGPA4") (class "Default")
      (node (ref "J3") (pin "52") (pinfunction "52_52") (pintype "bidirectional"))
    )
    (net (code "46") (name "XGPA5") (class "Default")
      (node (ref "J3") (pin "54") (pinfunction "54_54") (pintype "bidirectional"))
    )
    (net (code "47") (name "XGPA6") (class "Default")
      (node (ref "J4") (pin "63") (pinfunction "63_63") (pintype "bidirectional"))
    )
    (net (code "48") (name "XGPA15") (class "Default")
      (node (ref "IC2") (pin "4") (pinfunction "~{EN}_4") (pintype "bidirectional"))
      (node (ref "J3") (pin "55") (pinfunction "55_55") (pintype "bidirectional"))
      (node (ref "R13") (pin "2") (pinfunction "2_2") (pintype "passive"))
    )
    (net (code "49") (name "XGPA16") (class "Default")
      (node (ref "IC4") (pin "4") (pinfunction "~{EN}_4") (pintype "bidirectional"))
      (node (ref "J3") (pin "56") (pinfunction "56_56") (pintype "bidirectional"))
      (node (ref "R16") (pin "2") (pinfunction "2_2") (pintype "passive"))
    )
    (net (code "50") (name "XGPA17") (class "Default")
      (node (ref "J4") (pin "68") (pinfunction "68_68") (pintype "bidirectional"))
    )
    (net (code "51") (name "XGPA21") (class "Default")
      (node (ref "IC3") (pin "12") (pinfunction "CT_HPD_12") (pintype "bidirectional"))
      (node (ref "IC3") (pin "5") (pinfunction "LS_OE_5") (pintype "bidirectional"))
      (node (ref "J4") (pin "61") (pinfunction "61_61") (pintype "bidirectional"))
    )
    (net (code "52") (name "XGPB16") (class "Default")
      (node (ref "J4") (pin "66") (pinfunction "66_66") (pintype "bidirectional"))
    )
    (net (code "53") (name "XGPB22") (class "Default")
      (node (ref "J4") (pin "64") (pinfunction "64_64") (pintype "bidirectional"))
    )
    (net (code "54") (name "XGPC0") (class "Default")
      (node (ref "J4") (pin "57") (pinfunction "57_57") (pintype "bidirectional"))
    )
    (net (code "55") (name "XGPC25") (class "Default")
      (node (ref "J4") (pin "65") (pinfunction "65_65") (pintype "bidirectional"))
    )
    (net (code "56") (name "XGPD8") (class "Default")
      (node (ref "J4") (pin "58") (pinfunction "58_58") (pintype "bidirectional"))
    )
    (net (code "57") (name "XGPE30") (class "Default")
      (node (ref "J4") (pin "60") (pinfunction "60_60") (pintype "bidirectional"))
    )
    (net (code "58") (name "XGPE31") (class "Default")
      (node (ref "J4") (pin "67") (pinfunction "67_67") (pintype "bidirectional"))
    )
    (net (code "59") (name "XGPIO0") (class "Default")
      (node (ref "J4") (pin "12") (pinfunction "12_12") (pintype "bidirectional"))
      (node (ref "SV1") (pin "8") (pinfunction "8_8") (pintype "passive"))
    )
    (net (code "60") (name "XGPIO1") (class "Default")
      (node (ref "J4") (pin "13") (pinfunction "13_13") (pintype "bidirectional"))
      (node (ref "SV1") (pin "9") (pinfunction "9_9") (pintype "passive"))
    )
    (net (code "61") (name "XGPIO2") (class "Default")
      (node (ref "J4") (pin "14") (pinfunction "14_14") (pintype "bidirectional"))
      (node (ref "SV1") (pin "10") (pinfunction "10_10") (pintype "passive"))
    )
    (net (code "62") (name "XGPIO3") (class "Default")
      (node (ref "J4") (pin "16") (pinfunction "16_16") (pintype "bidirectional"))
      (node (ref "SV1") (pin "12") (pinfunction "12_12") (pintype "passive"))
    )
    (net (code "63") (name "XGPIO4") (class "Default")
      (node (ref "J4") (pin "37") (pinfunction "37_37") (pintype "bidirectional"))
      (node (ref "SV1") (pin "29") (pinfunction "29_29") (pintype "passive"))
    )
    (net (code "64") (name "XGPIO5") (class "Default")
      (node (ref "J4") (pin "40") (pinfunction "40_40") (pintype "bidirectional"))
      (node (ref "SV1") (pin "30") (pinfunction "30_30") (pintype "passive"))
    )
    (net (code "65") (name "XGPIO6") (class "Default")
      (node (ref "J4") (pin "39") (pinfunction "39_39") (pintype "bidirectional"))
      (node (ref "SV1") (pin "31") (pinfunction "31_31") (pintype "passive"))
    )
    (net (code "66") (name "XGPIO7") (class "Default")
      (node (ref "J4") (pin "59") (pinfunction "59_59") (pintype "bidirectional"))
      (node (ref "SV1") (pin "32") (pinfunction "32_32") (pintype "passive"))
    )
    (net (code "67") (name "XHDMI_CEC") (class "Default")
      (node (ref "IC3") (pin "1") (pinfunction "CEC_A_1") (pintype "bidirectional"))
      (node (ref "J3") (pin "33") (pinfunction "33_33") (pintype "bidirectional"))
    )
    (net (code "68") (name "XHDMI_HPD") (class "Default")
      (node (ref "IC3") (pin "4") (pinfunction "HPD_A-_4") (pintype "bidirectional"))
      (node (ref "J3") (pin "34") (pinfunction "34_34") (pintype "bidirectional"))
    )
    (net (code "69") (name "XHDMI_I2C_SCL") (class "Default")
      (node (ref "IC3") (pin "2") (pinfunction "SCL_A_2") (pintype "bidirectional"))
      (node (ref "J4") (pin "33") (pinfunction "33_33") (pintype "bidirectional"))
    )
    (net (code "70") (name "XHDMI_I2C_SDA") (class "Default")
      (node (ref "IC3") (pin "3") (pinfunction "SDA_A_3") (pintype "bidirectional"))
      (node (ref "J4") (pin "34") (pinfunction "34_34") (pintype "bidirectional"))
    )
    (net (code "71") (name "XHDMI_TX0_N") (class "Default")
      (node (ref "IC3") (pin "17") (pinfunction "D0-_17") (pintype "bidirectional"))
      (node (ref "J3") (pin "39") (pinfunction "39_39") (pintype "bidirectional"))
      (node (ref "J7") (pin "9") (pinfunction "D0-_9") (pintype "bidirectional"))
    )
    (net (code "72") (name "XHDMI_TX0_P") (class "Default")
      (node (ref "IC3") (pin "18") (pinfunction "D0+_18") (pintype "bidirectional"))
      (node (ref "J3") (pin "40") (pinfunction "40_40") (pintype "bidirectional"))
      (node (ref "J7") (pin "7") (pinfunction "D0+_7") (pintype "bidirectional"))
    )
    (net (code "73") (name "XHDMI_TX1_N") (class "Default")
      (node (ref "IC3") (pin "20") (pinfunction "D1-_20") (pintype "bidirectional"))
      (node (ref "J3") (pin "37") (pinfunction "37_37") (pintype "bidirectional"))
      (node (ref "J7") (pin "6") (pinfunction "D1-_6") (pintype "bidirectional"))
    )
    (net (code "74") (name "XHDMI_TX1_P") (class "Default")
      (node (ref "IC3") (pin "21") (pinfunction "D1+_21") (pintype "bidirectional"))
      (node (ref "J3") (pin "38") (pinfunction "38_38") (pintype "bidirectional"))
      (node (ref "J7") (pin "4") (pinfunction "D1+_4") (pintype "bidirectional"))
    )
    (net (code "75") (name "XHDMI_TX2_N") (class "Default")
      (node (ref "IC3") (pin "22") (pinfunction "D2-_22") (pintype "bidirectional"))
      (node (ref "J3") (pin "35") (pinfunction "35_35") (pintype "bidirectional"))
      (node (ref "J7") (pin "3") (pinfunction "D2-_3") (pintype "bidirectional"))
    )
    (net (code "76") (name "XHDMI_TX2_P") (class "Default")
      (node (ref "IC3") (pin "23") (pinfunction "D2+_23") (pintype "bidirectional"))
      (node (ref "J3") (pin "36") (pinfunction "36_36") (pintype "bidirectional"))
      (node (ref "J7") (pin "1") (pinfunction "D2+_1") (pintype "bidirectional"))
    )
    (net (code "77") (name "XHDMI_TXC_N") (class "Default")
      (node (ref "IC3") (pin "15") (pinfunction "CLK-_15") (pintype "input"))
      (node (ref "J3") (pin "41") (pinfunction "41_41") (pintype "bidirectional"))
      (node (ref "J7") (pin "12") (pinfunction "CLK-_12") (pintype "bidirectional"))
    )
    (net (code "78") (name "XHDMI_TXC_P") (class "Default")
      (node (ref "IC3") (pin "16") (pinfunction "CLK+_16") (pintype "input"))
      (node (ref "J3") (pin "42") (pinfunction "42_42") (pintype "bidirectional"))
      (node (ref "J7") (pin "10") (pinfunction "CLK+_10") (pintype "bidirectional"))
    )
    (net (code "79") (name "XI2C_SCL0") (class "Default")
      (node (ref "J4") (pin "31") (pinfunction "31_31") (pintype "bidirectional"))
      (node (ref "SV1") (pin "27") (pinfunction "27_27") (pintype "passive"))
    )
    (net (code "80") (name "XI2C_SCL1") (class "Default")
      (node (ref "J4") (pin "29") (pinfunction "29_29") (pintype "bidirectional"))
      (node (ref "SV1") (pin "25") (pinfunction "25_25") (pintype "passive"))
    )
    (net (code "81") (name "XI2C_SCL2") (class "Default")
      (node (ref "J4") (pin "27") (pinfunction "27_27") (pintype "bidirectional"))
      (node (ref "SV1") (pin "23") (pinfunction "23_23") (pintype "passive"))
    )
    (net (code "82") (name "XI2C_SDA0") (class "Default")
      (node (ref "J4") (pin "32") (pinfunction "32_32") (pintype "bidirectional"))
      (node (ref "SV1") (pin "28") (pinfunction "28_28") (pintype "passive"))
    )
    (net (code "83") (name "XI2C_SDA1") (class "Default")
      (node (ref "J4") (pin "30") (pinfunction "30_30") (pintype "bidirectional"))
      (node (ref "SV1") (pin "26") (pinfunction "26_26") (pintype "passive"))
    )
    (net (code "84") (name "XI2C_SDA2") (class "Default")
      (node (ref "J4") (pin "28") (pinfunction "28_28") (pintype "bidirectional"))
      (node (ref "SV1") (pin "24") (pinfunction "24_24") (pintype "passive"))
    )
    (net (code "85") (name "XI2S0_BCLK") (class "Default")
      (node (ref "J4") (pin "19") (pinfunction "19_19") (pintype "bidirectional"))
      (node (ref "SV1") (pin "15") (pinfunction "15_15") (pintype "passive"))
    )
    (net (code "86") (name "XI2S0_DIN") (class "Default")
      (node (ref "J4") (pin "18") (pinfunction "18_18") (pintype "bidirectional"))
      (node (ref "SV1") (pin "14") (pinfunction "14_14") (pintype "passive"))
    )
    (net (code "87") (name "XI2S0_DOUT") (class "Default")
      (node (ref "J4") (pin "17") (pinfunction "17_17") (pintype "bidirectional"))
      (node (ref "SV1") (pin "13") (pinfunction "13_13") (pintype "passive"))
    )
    (net (code "88") (name "XI2S0_LRCLK") (class "Default")
      (node (ref "J4") (pin "15") (pinfunction "15_15") (pintype "bidirectional"))
      (node (ref "SV1") (pin "11") (pinfunction "11_11") (pintype "passive"))
    )
    (net (code "89") (name "XI2S0_MCLK") (class "Default")
      (node (ref "J4") (pin "20") (pinfunction "20_20") (pintype "bidirectional"))
      (node (ref "SV1") (pin "16") (pinfunction "16_16") (pintype "passive"))
    )
    (net (code "90") (name "XMIPICSI_D0_N") (class "Default")
      (node (ref "J3") (pin "11") (pinfunction "11_11") (pintype "bidirectional"))
    )
    (net (code "91") (name "XMIPICSI_D0_P") (class "Default")
      (node (ref "J3") (pin "12") (pinfunction "12_12") (pintype "bidirectional"))
    )
    (net (code "92") (name "XMIPICSI_D1_N") (class "Default")
      (node (ref "J3") (pin "13") (pinfunction "13_13") (pintype "bidirectional"))
    )
    (net (code "93") (name "XMIPICSI_D1_P") (class "Default")
      (node (ref "J3") (pin "14") (pinfunction "14_14") (pintype "bidirectional"))
    )
    (net (code "94") (name "XMIPICSI_D2_N") (class "Default")
      (node (ref "J3") (pin "15") (pinfunction "15_15") (pintype "bidirectional"))
    )
    (net (code "95") (name "XMIPICSI_D2_P") (class "Default")
      (node (ref "J3") (pin "16") (pinfunction "16_16") (pintype "bidirectional"))
    )
    (net (code "96") (name "XMIPICSI_D3_N") (class "Default")
      (node (ref "J3") (pin "17") (pinfunction "17_17") (pintype "bidirectional"))
    )
    (net (code "97") (name "XMIPICSI_D3_P") (class "Default")
      (node (ref "J3") (pin "18") (pinfunction "18_18") (pintype "bidirectional"))
    )
    (net (code "98") (name "XMIPICSI_DCLK_N") (class "Default")
      (node (ref "J3") (pin "9") (pinfunction "9_9") (pintype "bidirectional"))
    )
    (net (code "99") (name "XMIPICSI_DCLK_P") (class "Default")
      (node (ref "J3") (pin "10") (pinfunction "10_10") (pintype "bidirectional"))
    )
    (net (code "100") (name "XMIPIDSI_D0_N") (class "Default")
      (node (ref "J3") (pin "23") (pinfunction "23_23") (pintype "bidirectional"))
    )
    (net (code "101") (name "XMIPIDSI_D0_P") (class "Default")
      (node (ref "J3") (pin "24") (pinfunction "24_24") (pintype "bidirectional"))
    )
    (net (code "102") (name "XMIPIDSI_D1_N") (class "Default")
      (node (ref "J3") (pin "25") (pinfunction "25_25") (pintype "bidirectional"))
    )
    (net (code "103") (name "XMIPIDSI_D1_P") (class "Default")
      (node (ref "J3") (pin "26") (pinfunction "26_26") (pintype "bidirectional"))
    )
    (net (code "104") (name "XMIPIDSI_D2_N") (class "Default")
      (node (ref "J3") (pin "27") (pinfunction "27_27") (pintype "bidirectional"))
    )
    (net (code "105") (name "XMIPIDSI_D2_P") (class "Default")
      (node (ref "J3") (pin "28") (pinfunction "28_28") (pintype "bidirectional"))
    )
    (net (code "106") (name "XMIPIDSI_D3_N") (class "Default")
      (node (ref "J3") (pin "29") (pinfunction "29_29") (pintype "bidirectional"))
    )
    (net (code "107") (name "XMIPIDSI_D3_P") (class "Default")
      (node (ref "J3") (pin "30") (pinfunction "30_30") (pintype "bidirectional"))
    )
    (net (code "108") (name "XMIPIDSI_DCLK_N") (class "Default")
      (node (ref "J3") (pin "21") (pinfunction "21_21") (pintype "bidirectional"))
    )
    (net (code "109") (name "XMIPIDSI_DCLK_P") (class "Default")
      (node (ref "J3") (pin "22") (pinfunction "22_22") (pintype "bidirectional"))
    )
    (net (code "110") (name "XNRESET") (class "Default")
      (node (ref "J4") (pin "11") (pinfunction "11_11") (pintype "bidirectional"))
      (node (ref "R12") (pin "2") (pinfunction "2_2") (pintype "passive"))
    )
    (net (code "111") (name "XOTG_D_N") (class "Default")
      (node (ref "J2") (pin "D-") (pinfunction "D-_D-") (pintype "bidirectional"))
      (node (ref "J3") (pin "45") (pinfunction "45_45") (pintype "bidirectional"))
    )
    (net (code "112") (name "XOTG_D_P") (class "Default")
      (node (ref "J2") (pin "D+") (pinfunction "D+_D+") (pintype "bidirectional"))
      (node (ref "J3") (pin "46") (pinfunction "46_46") (pintype "bidirectional"))
    )
    (net (code "113") (name "XOTG_ID") (class "Default")
      (node (ref "J2") (pin "ID") (pinfunction "ID_ID") (pintype "bidirectional"))
      (node (ref "J3") (pin "50") (pinfunction "50_50") (pintype "bidirectional"))
      (node (ref "R14") (pin "1") (pinfunction "1_1") (pintype "passive"))
    )
    (net (code "114") (name "XPGC27") (class "Default")
      (node (ref "J4") (pin "62") (pinfunction "62_62") (pintype "bidirectional"))
    )
    (net (code "115") (name "XPWERKEY") (class "Default")
      (node (ref "J4") (pin "9") (pinfunction "9_9") (pintype "bidirectional"))
      (node (ref "R9") (pin "2") (pinfunction "2_2") (pintype "passive"))
    )
    (net (code "116") (name "XPWM0") (class "Default")
      (node (ref "J4") (pin "26") (pinfunction "26_26") (pintype "bidirectional"))
      (node (ref "SV1") (pin "22") (pinfunction "22_22") (pintype "passive"))
    )
    (net (code "117") (name "XPWM1") (class "Default")
      (node (ref "J4") (pin "25") (pinfunction "25_25") (pintype "bidirectional"))
      (node (ref "SV1") (pin "21") (pinfunction "21_21") (pintype "passive"))
    )
    (net (code "118") (name "XSD0_CLK") (class "Default")
      (node (ref "J4") (pin "49") (pinfunction "49_49") (pintype "bidirectional"))
    )
    (net (code "119") (name "XSD0_CMD") (class "Default")
      (node (ref "J4") (pin "47") (pinfunction "47_47") (pintype "bidirectional"))
    )
    (net (code "120") (name "XSD0_D0") (class "Default")
      (node (ref "J4") (pin "52") (pinfunction "52_52") (pintype "bidirectional"))
    )
    (net (code "121") (name "XSD0_D1") (class "Default")
      (node (ref "J4") (pin "51") (pinfunction "51_51") (pintype "bidirectional"))
    )
    (net (code "122") (name "XSD0_D2") (class "Default")
      (node (ref "J4") (pin "50") (pinfunction "50_50") (pintype "bidirectional"))
    )
    (net (code "123") (name "XSD0_D3") (class "Default")
      (node (ref "J4") (pin "48") (pinfunction "48_48") (pintype "bidirectional"))
    )
    (net (code "124") (name "XSPI_CLK") (class "Default")
      (node (ref "J4") (pin "23") (pinfunction "23_23") (pintype "bidirectional"))
      (node (ref "SV1") (pin "19") (pinfunction "19_19") (pintype "passive"))
    )
    (net (code "125") (name "XSPI_CS") (class "Default")
      (node (ref "J4") (pin "24") (pinfunction "24_24") (pintype "bidirectional"))
      (node (ref "SV1") (pin "20") (pinfunction "20_20") (pintype "passive"))
    )
    (net (code "126") (name "XSPI_MISO") (class "Default")
      (node (ref "J4") (pin "21") (pinfunction "21_21") (pintype "bidirectional"))
      (node (ref "SV1") (pin "17") (pinfunction "17_17") (pintype "passive"))
    )
    (net (code "127") (name "XSPI_MOSI") (class "Default")
      (node (ref "J4") (pin "22") (pinfunction "22_22") (pintype "bidirectional"))
      (node (ref "SV1") (pin "18") (pinfunction "18_18") (pintype "passive"))
    )
    (net (code "128") (name "XUART_RX0") (class "Default")
      (node (ref "J4") (pin "46") (pinfunction "46_46") (pintype "bidirectional"))
      (node (ref "SV1") (pin "36") (pinfunction "36_36") (pintype "passive"))
    )
    (net (code "129") (name "XUART_RX1") (class "Default")
      (node (ref "J4") (pin "44") (pinfunction "44_44") (pintype "bidirectional"))
      (node (ref "SV1") (pin "34") (pinfunction "34_34") (pintype "passive"))
    )
    (net (code "130") (name "XUART_TX0") (class "Default")
      (node (ref "J4") (pin "45") (pinfunction "45_45") (pintype "bidirectional"))
      (node (ref "SV1") (pin "35") (pinfunction "35_35") (pintype "passive"))
    )
    (net (code "131") (name "XUART_TX1") (class "Default")
      (node (ref "J4") (pin "43") (pinfunction "43_43") (pintype "bidirectional"))
      (node (ref "SV1") (pin "33") (pinfunction "33_33") (pintype "passive"))
    )
    (net (code "132") (name "XUSBH_D_N") (class "Default")
      (node (ref "J3") (pin "47") (pinfunction "47_47") (pintype "bidirectional"))
      (node (ref "J5") (pin "2") (pinfunction "D-_2") (pintype "bidirectional"))
    )
    (net (code "133") (name "XUSBH_D_P") (class "Default")
      (node (ref "J3") (pin "48") (pinfunction "48_48") (pintype "bidirectional"))
      (node (ref "J5") (pin "3") (pinfunction "D+_3") (pintype "bidirectional"))
    )
    (net (code "134") (name "XVDDPWRON") (class "Default")
      (node (ref "J4") (pin "38") (pinfunction "38_38") (pintype "bidirectional"))
      (node (ref "R15") (pin "2") (pinfunction "2_2") (pintype "passive"))
    )
    (net (code "135") (name "unconnected-(IC2-~{OC}-Pad3)") (class "Default")
      (node (ref "IC2") (pin "3") (pinfunction "~{OC}_3") (pintype "bidirectional"))
    )
    (net (code "136") (name "unconnected-(IC4-~{OC}-Pad3)") (class "Default")
      (node (ref "IC4") (pin "3") (pinfunction "~{OC}_3") (pintype "bidirectional"))
    )
    (net (code "137") (name "unconnected-(J3-Pad49)") (class "Default")
      (node (ref "J3") (pin "49") (pinfunction "49_49") (pintype "bidirectional"))
    )
    (net (code "138") (name "unconnected-(J3-Pad51)") (class "Default")
      (node (ref "J3") (pin "51") (pinfunction "51_51") (pintype "bidirectional"))
    )
    (net (code "139") (name "unconnected-(J3-Pad53)") (class "Default")
      (node (ref "J3") (pin "53") (pinfunction "53_53") (pintype "bidirectional"))
    )
    (net (code "140") (name "unconnected-(J3-Pad57)") (class "Default")
      (node (ref "J3") (pin "57") (pinfunction "57_57") (pintype "bidirectional"))
    )
    (net (code "141") (name "unconnected-(J3-Pad58)") (class "Default")
      (node (ref "J3") (pin "58") (pinfunction "58_58") (pintype "bidirectional"))
    )
    (net (code "142") (name "unconnected-(J3-Pad61)") (class "Default")
      (node (ref "J3") (pin "61") (pinfunction "61_61") (pintype "bidirectional"))
    )
    (net (code "143") (name "unconnected-(J3-Pad62)") (class "Default")
      (node (ref "J3") (pin "62") (pinfunction "62_62") (pintype "bidirectional"))
    )
    (net (code "144") (name "unconnected-(J4-Pad7)") (class "Default")
      (node (ref "J4") (pin "7") (pinfunction "7_7") (pintype "bidirectional"))
    )
    (net (code "145") (name "unconnected-(J4-Pad53)") (class "Default")
      (node (ref "J4") (pin "53") (pinfunction "53_53") (pintype "bidirectional"))
    )
    (net (code "146") (name "unconnected-(J4-Pad69)") (class "Default")
      (node (ref "J4") (pin "69") (pinfunction "69_69") (pintype "bidirectional"))
    )
    (net (code "147") (name "unconnected-(J6-1-PadDTR)") (class "Default")
      (node (ref "J6") (pin "DTR") (pinfunction "1_DTR") (pintype "passive"))
    )
    (net (code "148") (name "unconnected-(J6-4-PadVCC)") (class "Default")
      (node (ref "J6") (pin "VCC") (pinfunction "4_VCC") (pintype "passive"))
    )
    (net (code "149") (name "unconnected-(J6-5-PadCTS)") (class "Default")
      (node (ref "J6") (pin "CTS") (pinfunction "5_CTS") (pintype "passive"))
    )
    (net (code "150") (name "unconnected-(J7-UTILITY-Pad14)") (class "Default")
      (node (ref "J7") (pin "14") (pinfunction "UTILITY_14") (pintype "bidirectional"))
    )
    (net (code "151") (name "unconnected-(S3-Pad3)") (class "Default")
      (node (ref "S3") (pin "3") (pinfunction "3_3") (pintype "bidirectional"))
    )
    (net (code "152") (name "unconnected-(S3-Pad6)") (class "Default")
      (node (ref "S3") (pin "6") (pinfunction "6_6") (pintype "bidirectional"))
    )
  )
)
